# rs485.net
KiCad netlist of a schematic drawn in Altium Designer
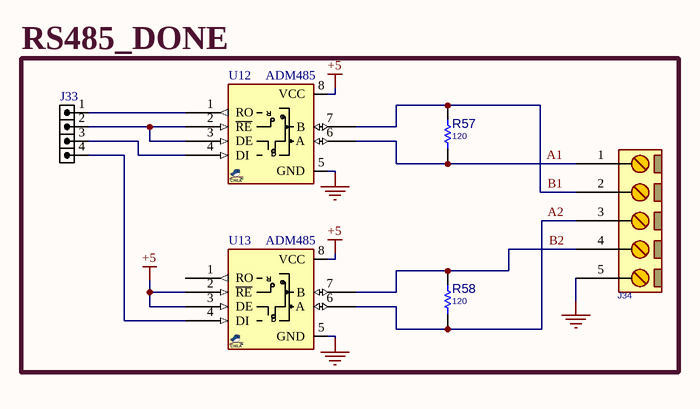
[diagram p0: rs485.SchDoc]

(export (version "E")
  (design (tool "Eeschema 10.0.6"))
  (components
    (comp (ref "J33")
      (value "HDR1X4")
      (footprint "HDR_M_1X4")
      (description "CONN, HEADER, Male, pitch: 2.54mm, 4POS")
      (libsource (lib "conn_header_2.54mm_st") (part "HDR_M_1X4"))
    )
    (comp (ref "J34")
      (value "CONN_TB5")
      (footprint "TBG_5")
      (description "CONN, TERMINAL BLOCK, 5.08mm pitch")
      (libsource (lib "conn_power_terminalB") (part "CONN_TB5"))
    )
    (comp (ref "R57")
      (value "120")
      (footprint "R025W_AX04")
      (description "RESISTOR, THD")
      (fields (field (name "MANF_P#") "RK73H1ETTP4701F") (field (name "MANF") "KOA SPEER"))
      (libsource (lib "passive_thd") (part "RES_THD"))
    )
    (comp (ref "R58")
      (value "120")
      (footprint "R025W_AX04")
      (description "RESISTOR, THD")
      (fields (field (name "MANF_P#") "RK73H1ETTP4701F") (field (name "MANF") "KOA SPEER"))
      (libsource (lib "passive_thd") (part "RES_THD"))
    )
    (comp (ref "U12")
      (value "ADM485")
      (footprint "DIP_8")
      (description "RS-485 Transceiver, 5V, DIP-8, ±7V Ground Difference Between Devices on the Bus")
      (fields (field (name "MANF_P#") "ADM485AN") (field (name "MANF") "Analog Devices"))
      (libsource (lib "AvrDevelopmentBoard") (part "ADM485_DIP8"))
    )
    (comp (ref "U13")
      (value "ADM485")
      (footprint "DIP_8")
      (description "RS-485 Transceiver, 5V, DIP-8, ±7V Ground Difference Between Devices on the Bus")
      (fields (field (name "MANF_P#") "ADM485AN") (field (name "MANF") "Analog Devices"))
      (libsource (lib "AvrDevelopmentBoard") (part "ADM485_DIP8"))
    )
  )
  (nets
    (net (code "1") (name "+5") (class "Default")
      (node (ref "U12") (pin "8") (pinfunction "VCC_8") (pintype "passive"))
      (node (ref "U13") (pin "2") (pinfunction "~{RE}_2") (pintype "input"))
      (node (ref "U13") (pin "3") (pinfunction "DE_3") (pintype "input"))
      (node (ref "U13") (pin "8") (pinfunction "VCC_8") (pintype "passive"))
    )
    (net (code "2") (name "/A1") (class "Default")
      (node (ref "J34") (pin "1") (pinfunction "1_1") (pintype "passive"))
      (node (ref "R57") (pin "1") (pinfunction "1_1") (pintype "passive"))
      (node (ref "U12") (pin "6") (pinfunction "A_6") (pintype "bidirectional"))
    )
    (net (code "3") (name "/A2") (class "Default")
      (node (ref "J34") (pin "3") (pinfunction "3_3") (pintype "passive"))
      (node (ref "R58") (pin "1") (pinfunction "1_1") (pintype "passive"))
      (node (ref "U13") (pin "6") (pinfunction "A_6") (pintype "bidirectional"))
    )
    (net (code "4") (name "/B1") (class "Default")
      (node (ref "J34") (pin "2") (pinfunction "2_2") (pintype "passive"))
      (node (ref "R57") (pin "2") (pinfunction "2_2") (pintype "passive"))
      (node (ref "U12") (pin "7") (pinfunction "B_7") (pintype "bidirectional"))
    )
    (net (code "5") (name "/B2") (class "Default")
      (node (ref "J34") (pin "4") (pinfunction "4_4") (pintype "passive"))
      (node (ref "R58") (pin "2") (pinfunction "2_2") (pintype "passive"))
      (node (ref "U13") (pin "7") (pinfunction "B_7") (pintype "bidirectional"))
    )
    (net (code "6") (name "GND") (class "Default")
      (node (ref "J34") (pin "5") (pinfunction "5_5") (pintype "passive"))
      (node (ref "U12") (pin "5") (pinfunction "GND_5") (pintype "passive"))
      (node (ref "U13") (pin "5") (pinfunction "GND_5") (pintype "passive"))
    )
    (net (code "7") (name "Net-(U12-DE)") (class "Default")
      (node (ref "J33") (pin "2") (pinfunction "2_2") (pintype "passive"))
      (node (ref "U12") (pin "2") (pinfunction "~{RE}_2") (pintype "input"))
      (node (ref "U12") (pin "3") (pinfunction "DE_3") (pintype "input"))
    )
    (net (code "8") (name "Net-(U12-DI)") (class "Default")
      (node (ref "J33") (pin "3") (pinfunction "3_3") (pintype "passive"))
      (node (ref "U12") (pin "4") (pinfunction "DI_4") (pintype "input"))
    )
    (net (code "9") (name "Net-(U12-RO)") (class "Default")
      (node (ref "J33") (pin "1") (pinfunction "1_1") (pintype "passive"))
      (node (ref "U12") (pin "1") (pinfunction "RO_1") (pintype "output"))
    )
    (net (code "10") (name "Net-(U13-DI)") (class "Default")
      (node (ref "J33") (pin "4") (pinfunction "4_4") (pintype "passive"))
      (node (ref "U13") (pin "4") (pinfunction "DI_4") (pintype "input"))
    )
    (net (code "11") (name "unconnected-(U13-RO-Pad1)") (class "Default")
      (node (ref "U13") (pin "1") (pinfunction "RO_1") (pintype "output"))
    )
  )
)
